# smart-home-weather-station-v1.net
KiCad netlist of a schematic drawn in EasyEDA Pro
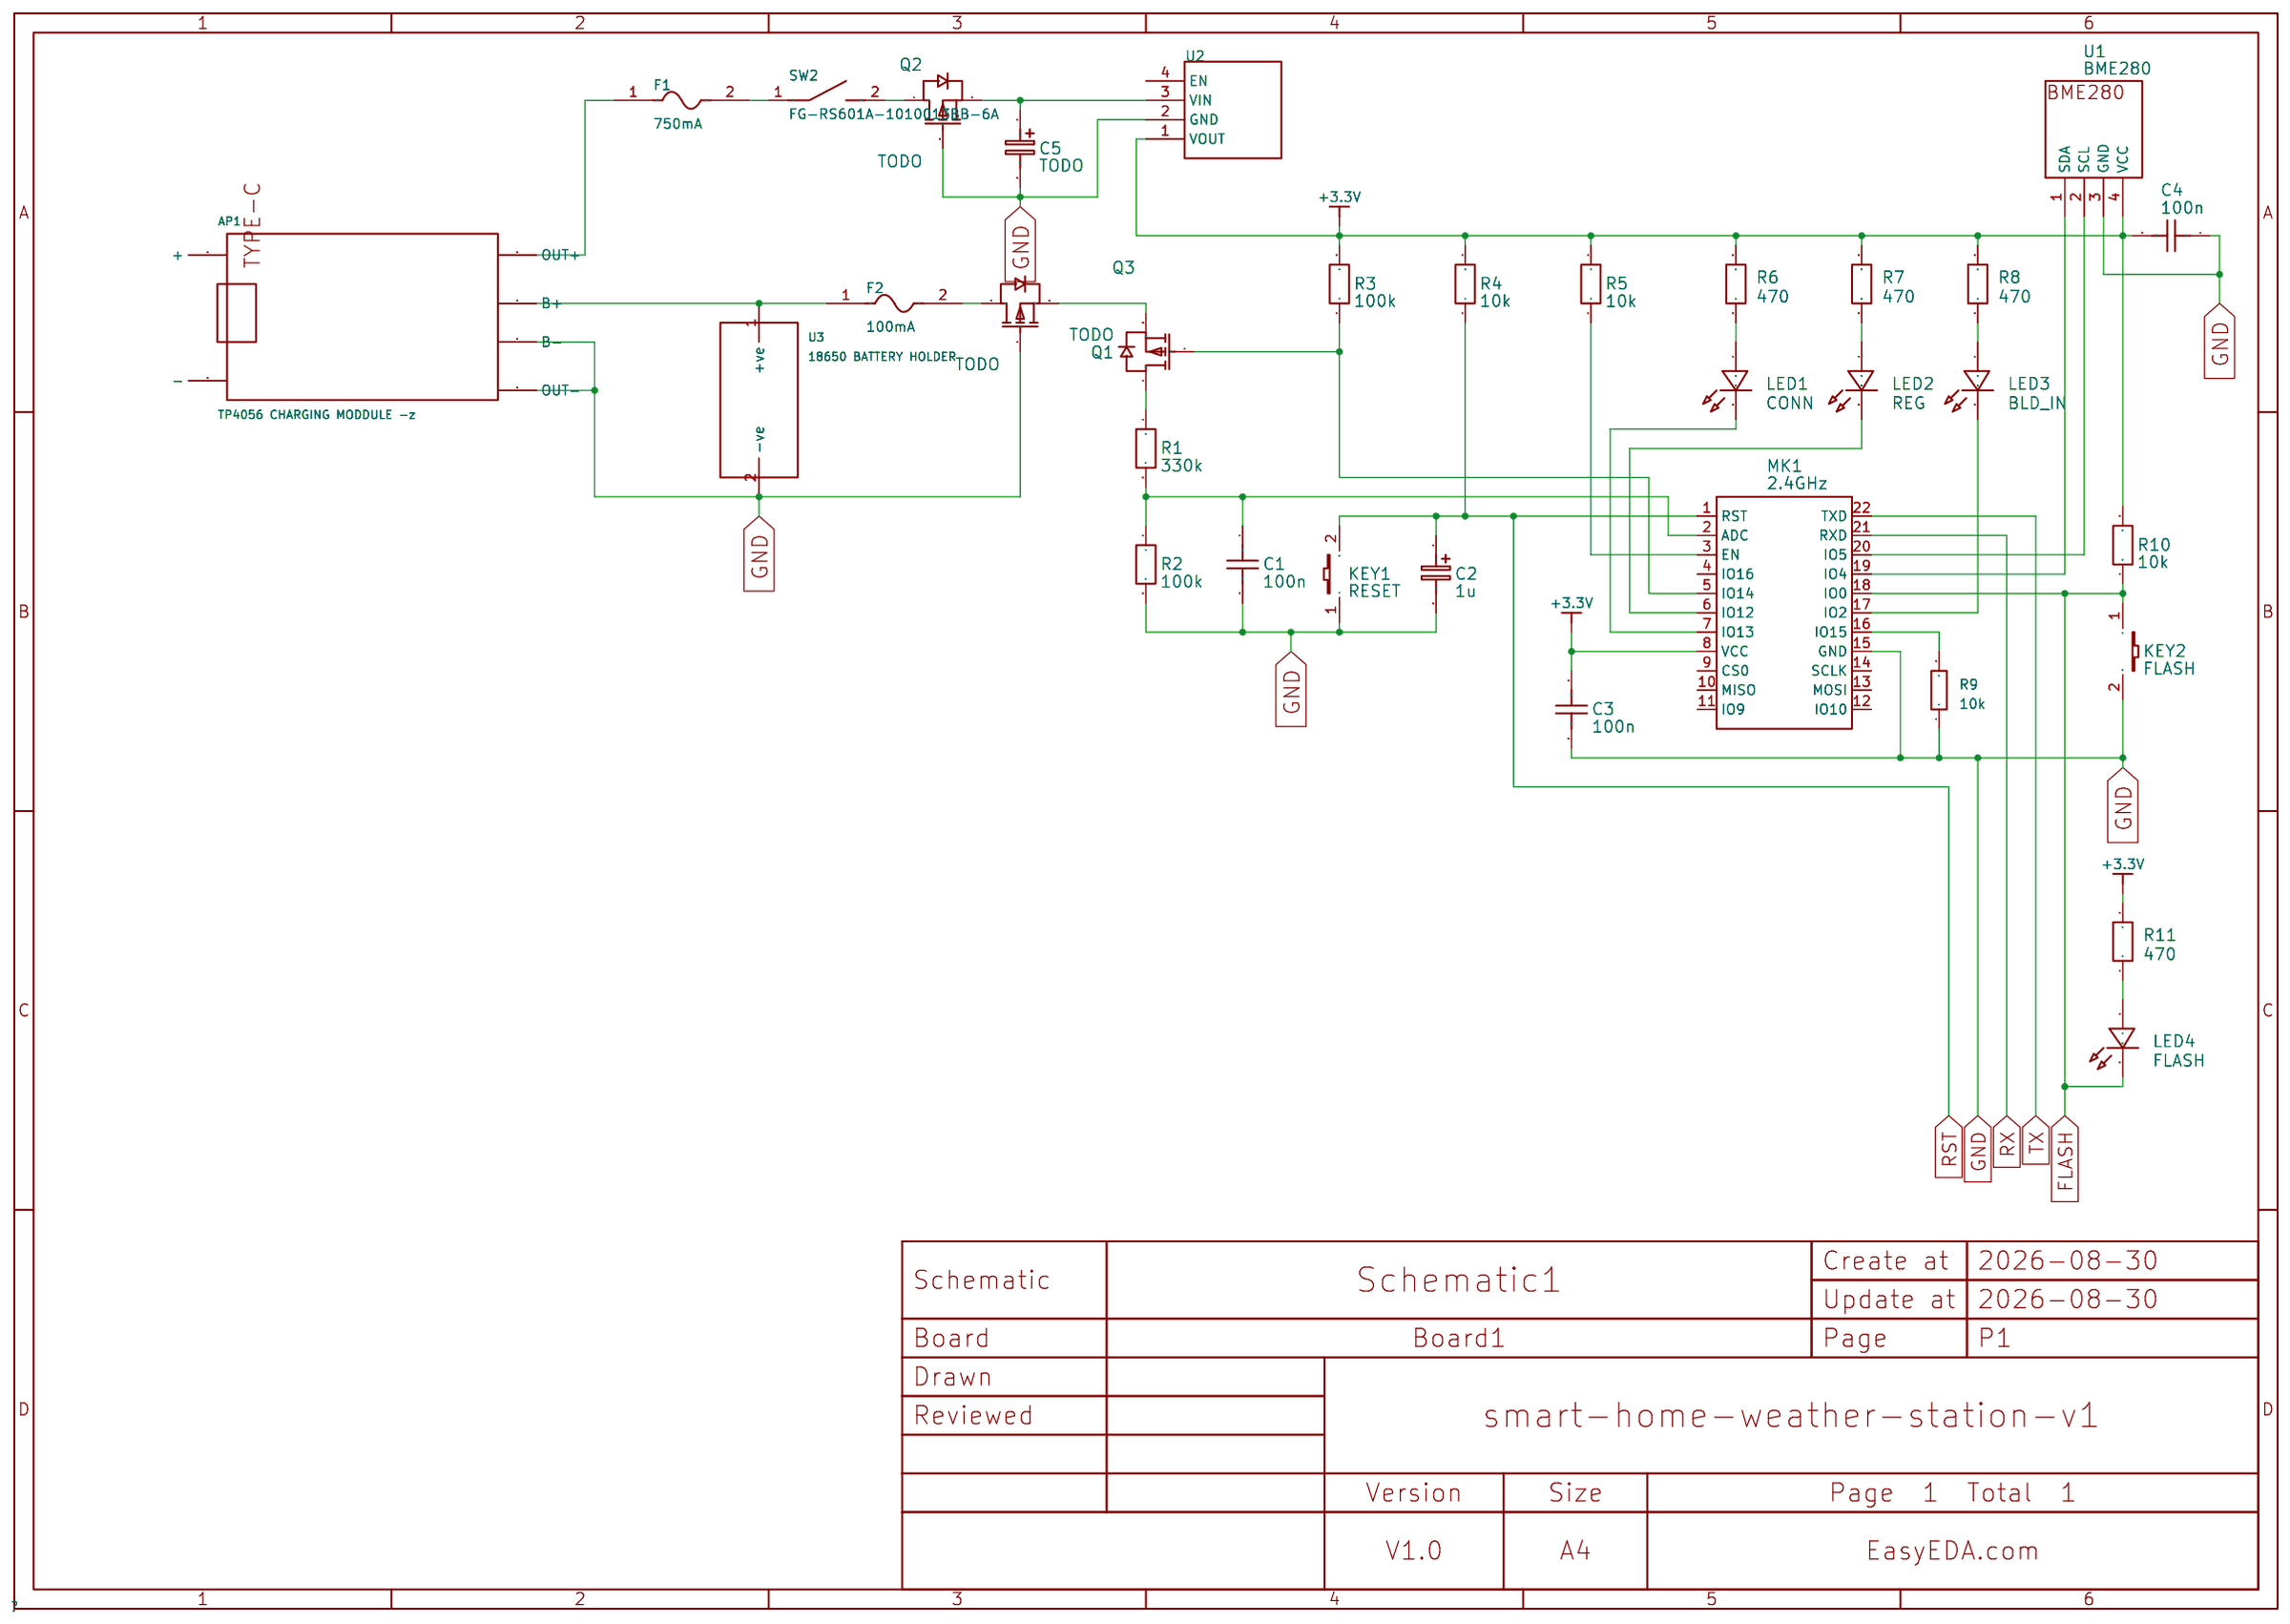
[diagram p0: schematic sheet]

(export (version "E")
  (design (tool "Eeschema 10.0.6"))
  (components
    (comp (ref "AP1")
      (value "TP4056 CHARGING MODDULE -z")
      (footprint "easyedapro:TP4056-CHARGING-MODULE_TP4056")
      (fields (field (name "Manufacturer Part") "TP4056"))
      (libsource (lib "easyedapro") (part "TP4056 CHARGING MODDULE -z"))
    )
    (comp (ref "C1")
      (value "100n")
      (footprint "easyedapro:C0603")
      (libsource (lib "easyedapro") (part "100n"))
    )
    (comp (ref "C2")
      (value "1u")
      (footprint "easyedapro:CASE-A_3216")
      (libsource (lib "easyedapro") (part "1u"))
    )
    (comp (ref "C3")
      (value "100n")
      (footprint "easyedapro:C0603")
      (libsource (lib "easyedapro") (part "100n"))
    )
    (comp (ref "C4")
      (value "100n")
      (footprint "easyedapro:C0603")
      (libsource (lib "easyedapro") (part "100n"))
    )
    (comp (ref "C5")
      (value "TODO")
      (footprint "easyedapro:CASE-A_3216")
      (libsource (lib "easyedapro") (part "1u"))
    )
    (comp (ref "F1")
      (value "750mA")
      (footprint "easyedapro:F1210")
      (fields (field (name "Manufacturer Part") "1210L150/16WR"))
      (libsource (lib "easyedapro") (part "1210L150/16WR_C9900015772"))
    )
    (comp (ref "F2")
      (value "100mA")
      (footprint "easyedapro:F1210")
      (fields (field (name "Manufacturer Part") "1210L150/16WR"))
      (libsource (lib "easyedapro") (part "1210L150/16WR_C9900015772"))
    )
    (comp (ref "KEY1")
      (value "RESET")
      (footprint "easyedapro:KEY-SMD_2P-L6.2-W3.6-LS8.0")
      (fields (field (name "Manufacturer Part") "K2-1107ST-A4SW-06"))
      (libsource (lib "easyedapro") (part "RESET"))
    )
    (comp (ref "KEY2")
      (value "FLASH")
      (footprint "easyedapro:KEY-SMD_2P-L6.2-W3.6-LS8.0")
      (fields (field (name "Manufacturer Part") "K2-1107ST-A4SW-06"))
      (libsource (lib "") (part "FLASH_1"))
    )
    (comp (ref "LED1")
      (value "CONN")
      (footprint "easyedapro:LED0603_RED")
      (fields
        (field (name "Manufacturer Part") "19-217/R6C-AL1M2VY/3T")
        (field (name "Manufacturer") "EVERLIGHT(台湾亿光)")
      )
      (libsource (lib "easyedapro") (part "FLASH"))
    )
    (comp (ref "LED2")
      (value "REG")
      (footprint "easyedapro:LED0603_RED")
      (fields
        (field (name "Manufacturer Part") "19-217/R6C-AL1M2VY/3T")
        (field (name "Manufacturer") "EVERLIGHT(台湾亿光)")
      )
      (libsource (lib "easyedapro") (part "FLASH"))
    )
    (comp (ref "LED3")
      (value "BLD_IN")
      (footprint "easyedapro:LED0603_RED")
      (fields
        (field (name "Manufacturer Part") "19-217/R6C-AL1M2VY/3T")
        (field (name "Manufacturer") "EVERLIGHT(台湾亿光)")
      )
      (libsource (lib "easyedapro") (part "FLASH"))
    )
    (comp (ref "LED4")
      (value "FLASH")
      (footprint "easyedapro:LED0603_RED")
      (fields
        (field (name "Manufacturer Part") "19-217/R6C-AL1M2VY/3T")
        (field (name "Manufacturer") "EVERLIGHT(台湾亿光)")
      )
      (libsource (lib "easyedapro") (part "FLASH"))
    )
    (comp (ref "MK1")
      (value "2.4GHz")
      (footprint "easyedapro:WIFIM-SMD_ESP-12E-BR")
      (fields (field (name "Manufacturer Part") "ESP-12E") (field (name "Manufacturer") "Ai-Thinker(安信可)"))
      (libsource (lib "easyedapro") (part "2.4GHz"))
    )
    (comp (ref "Q1")
      (value "TODO")
      (footprint "easyedapro:TO-263-2_L10.0-W9.1-P5.08-LS15.2-BR")
      (fields (field (name "Manufacturer Part") "IRF5210STRLPBF") (field (name "Manufacturer") "IR"))
      (libsource (lib "easyedapro") (part "TODO"))
    )
    (comp (ref "Q2")
      (value "TODO")
      (footprint "easyedapro:TO-263-2_L10.0-W9.1-P5.08-LS15.2-BR")
      (fields (field (name "Manufacturer Part") "IRF5210STRLPBF") (field (name "Manufacturer") "IR"))
      (libsource (lib "easyedapro") (part "TODO"))
    )
    (comp (ref "Q3")
      (value "TODO")
      (footprint "easyedapro:TO-263-2_L10.0-W9.1-P5.08-LS15.2-BR")
      (fields (field (name "Manufacturer Part") "IRF5210STRLPBF") (field (name "Manufacturer") "IR"))
      (libsource (lib "easyedapro") (part "TODO"))
    )
    (comp (ref "R1")
      (value "330k")
      (footprint "easyedapro:R0603")
      (libsource (lib "easyedapro") (part "330k"))
    )
    (comp (ref "R2")
      (value "100k")
      (footprint "easyedapro:R0603")
      (libsource (lib "easyedapro") (part "100k"))
    )
    (comp (ref "R3")
      (value "100k")
      (footprint "easyedapro:R0603")
      (libsource (lib "easyedapro") (part "100k"))
    )
    (comp (ref "R4") (value "10k") (footprint "easyedapro:R0603") (libsource (lib "easyedapro") (part "10k")))
    (comp (ref "R5") (value "10k") (footprint "easyedapro:R0603") (libsource (lib "easyedapro") (part "10k")))
    (comp (ref "R6") (value "470") (footprint "easyedapro:R0603") (libsource (lib "easyedapro") (part "470")))
    (comp (ref "R7") (value "470") (footprint "easyedapro:R0603") (libsource (lib "easyedapro") (part "470")))
    (comp (ref "R8") (value "470") (footprint "easyedapro:R0603") (libsource (lib "easyedapro") (part "470")))
    (comp (ref "R9") (value "10K") (footprint "easyedapro:R0603") (libsource (lib "easyedapro") (part "Res")))
    (comp (ref "R10")
      (value "10k")
      (footprint "easyedapro:R0603")
      (libsource (lib "easyedapro") (part "10k"))
    )
    (comp (ref "R11")
      (value "470")
      (footprint "easyedapro:R0603")
      (libsource (lib "easyedapro") (part "470"))
    )
    (comp (ref "SW2")
      (value "FG-RS601A-1010013BB-6A")
      (footprint "easyedapro:SW-TH_FG-RS601A-1010013BB-6A")
      (fields (field (name "Manufacturer") "FG(富港)"))
      (libsource (lib "easyedapro") (part "FG-RS601A-1010013BB-6A"))
    )
    (comp (ref "U1") (value "BME280") (libsource (lib "easyedapro") (part "BME280")))
    (comp (ref "U2")
      (value "~")
      (footprint "easyedapro:S8V9F3")
      (libsource (lib "easyedapro") (part "S8V9F3"))
    )
    (comp (ref "U3")
      (value "18650 BATTERY HOLDER")
      (footprint "easyedapro:18650 BATTERY HOLDER CB-18650-PC2")
      (libsource (lib "easyedapro") (part "18650 BATTERY HOLDER"))
    )
  )
  (nets
    (net (code "1") (name "+3.3V") (class "Default")
      (node (ref "C3") (pin "1") (pinfunction "1_1") (pintype "unspecified"))
      (node (ref "C4") (pin "2") (pinfunction "2_2") (pintype "unspecified"))
      (node (ref "MK1") (pin "8") (pinfunction "VCC_8") (pintype "unspecified"))
      (node (ref "R10") (pin "2") (pinfunction "2_2") (pintype "unspecified"))
      (node (ref "R11") (pin "2") (pinfunction "2_2") (pintype "unspecified"))
      (node (ref "R3") (pin "2") (pinfunction "2_2") (pintype "unspecified"))
      (node (ref "R4") (pin "2") (pinfunction "2_2") (pintype "unspecified"))
      (node (ref "R5") (pin "2") (pinfunction "2_2") (pintype "unspecified"))
      (node (ref "R6") (pin "2") (pinfunction "2_2") (pintype "unspecified"))
      (node (ref "R7") (pin "2") (pinfunction "2_2") (pintype "unspecified"))
      (node (ref "R8") (pin "2") (pinfunction "2_2") (pintype "unspecified"))
      (node (ref "U1") (pin "4") (pinfunction "VCC_4") (pintype "unspecified"))
      (node (ref "U2") (pin "1") (pinfunction "VOUT_1") (pintype "input"))
    )
    (net (code "2") (name "FLASH") (class "Default")
      (node (ref "KEY2") (pin "1") (pinfunction "1_1") (pintype "unspecified"))
      (node (ref "LED4") (pin "2") (pinfunction "2_2") (pintype "unspecified"))
      (node (ref "MK1") (pin "18") (pinfunction "IO0_18") (pintype "unspecified"))
      (node (ref "R10") (pin "1") (pinfunction "1_1") (pintype "unspecified"))
    )
    (net (code "3") (name "GND") (class "Default")
      (node (ref "AP1") (pin "2") (pinfunction "B-_2") (pintype "unspecified"))
      (node (ref "AP1") (pin "4") (pinfunction "OUT-_4") (pintype "unspecified"))
      (node (ref "C1") (pin "2") (pinfunction "2_2") (pintype "unspecified"))
      (node (ref "C2") (pin "2") (pinfunction "2_2") (pintype "unspecified"))
      (node (ref "C3") (pin "2") (pinfunction "2_2") (pintype "unspecified"))
      (node (ref "C4") (pin "1") (pinfunction "1_1") (pintype "unspecified"))
      (node (ref "C5") (pin "2") (pinfunction "2_2") (pintype "unspecified"))
      (node (ref "KEY1") (pin "1") (pinfunction "1_1") (pintype "unspecified"))
      (node (ref "KEY2") (pin "2") (pinfunction "2_2") (pintype "unspecified"))
      (node (ref "MK1") (pin "15") (pinfunction "GND_15") (pintype "unspecified"))
      (node (ref "Q2") (pin "1") (pinfunction "G_1") (pintype "unspecified"))
      (node (ref "Q3") (pin "1") (pinfunction "G_1") (pintype "unspecified"))
      (node (ref "R2") (pin "2") (pinfunction "2_2") (pintype "unspecified"))
      (node (ref "R9") (pin "1") (pinfunction "1_1") (pintype "input"))
      (node (ref "U1") (pin "3") (pinfunction "GND_3") (pintype "unspecified"))
      (node (ref "U2") (pin "2") (pinfunction "GND_2") (pintype "input"))
      (node (ref "U3") (pin "2") (pinfunction "-ve_2") (pintype "unspecified"))
    )
    (net (code "4") (name "Net-(AP1-B+)") (class "Default")
      (node (ref "AP1") (pin "1") (pinfunction "B+_1") (pintype "unspecified"))
      (node (ref "F2") (pin "1") (pinfunction "1_1") (pintype "unspecified"))
      (node (ref "U3") (pin "1") (pinfunction "+ve_1") (pintype "unspecified"))
    )
    (net (code "5") (name "Net-(AP1-OUT+)") (class "Default")
      (node (ref "AP1") (pin "3") (pinfunction "OUT+_3") (pintype "unspecified"))
      (node (ref "F1") (pin "1") (pinfunction "1_1") (pintype "unspecified"))
    )
    (net (code "6") (name "Net-(F1-Pad2)") (class "Default")
      (node (ref "F1") (pin "2") (pinfunction "2_2") (pintype "unspecified"))
      (node (ref "SW2") (pin "1") (pinfunction "1_1") (pintype "unspecified"))
    )
    (net (code "7") (name "Net-(LED1-Pad1)") (class "Default")
      (node (ref "LED1") (pin "1") (pinfunction "1_1") (pintype "unspecified"))
      (node (ref "R6") (pin "1") (pinfunction "1_1") (pintype "unspecified"))
    )
    (net (code "8") (name "Net-(LED2-Pad1)") (class "Default")
      (node (ref "LED2") (pin "1") (pinfunction "1_1") (pintype "unspecified"))
      (node (ref "R7") (pin "1") (pinfunction "1_1") (pintype "unspecified"))
    )
    (net (code "9") (name "Net-(LED3-Pad1)") (class "Default")
      (node (ref "LED3") (pin "1") (pinfunction "1_1") (pintype "unspecified"))
      (node (ref "R8") (pin "1") (pinfunction "1_1") (pintype "unspecified"))
    )
    (net (code "10") (name "Net-(LED4-Pad1)") (class "Default")
      (node (ref "LED4") (pin "1") (pinfunction "1_1") (pintype "unspecified"))
      (node (ref "R11") (pin "1") (pinfunction "1_1") (pintype "unspecified"))
    )
    (net (code "11") (name "Net-(MK1-ADC)") (class "Default")
      (node (ref "C1") (pin "1") (pinfunction "1_1") (pintype "unspecified"))
      (node (ref "MK1") (pin "2") (pinfunction "ADC_2") (pintype "unspecified"))
      (node (ref "R1") (pin "2") (pinfunction "2_2") (pintype "unspecified"))
      (node (ref "R2") (pin "1") (pinfunction "1_1") (pintype "unspecified"))
    )
    (net (code "12") (name "Net-(MK1-EN)") (class "Default")
      (node (ref "MK1") (pin "3") (pinfunction "EN_3") (pintype "unspecified"))
      (node (ref "R5") (pin "1") (pinfunction "1_1") (pintype "unspecified"))
    )
    (net (code "13") (name "Net-(MK1-IO2)") (class "Default")
      (node (ref "LED3") (pin "2") (pinfunction "2_2") (pintype "unspecified"))
      (node (ref "MK1") (pin "17") (pinfunction "IO2_17") (pintype "unspecified"))
    )
    (net (code "14") (name "Net-(MK1-IO4)") (class "Default")
      (node (ref "MK1") (pin "19") (pinfunction "IO4_19") (pintype "unspecified"))
      (node (ref "U1") (pin "1") (pinfunction "SDA_1") (pintype "unspecified"))
    )
    (net (code "15") (name "Net-(MK1-IO5)") (class "Default")
      (node (ref "MK1") (pin "20") (pinfunction "IO5_20") (pintype "unspecified"))
      (node (ref "U1") (pin "2") (pinfunction "SCL_2") (pintype "unspecified"))
    )
    (net (code "16") (name "Net-(MK1-IO12)") (class "Default")
      (node (ref "LED2") (pin "2") (pinfunction "2_2") (pintype "unspecified"))
      (node (ref "MK1") (pin "6") (pinfunction "IO12_6") (pintype "unspecified"))
    )
    (net (code "17") (name "Net-(MK1-IO13)") (class "Default")
      (node (ref "LED1") (pin "2") (pinfunction "2_2") (pintype "unspecified"))
      (node (ref "MK1") (pin "7") (pinfunction "IO13_7") (pintype "unspecified"))
    )
    (net (code "18") (name "Net-(MK1-IO14)") (class "Default")
      (node (ref "MK1") (pin "5") (pinfunction "IO14_5") (pintype "unspecified"))
      (node (ref "Q1") (pin "1") (pinfunction "G_1") (pintype "unspecified"))
      (node (ref "R3") (pin "1") (pinfunction "1_1") (pintype "unspecified"))
    )
    (net (code "19") (name "Net-(MK1-IO15)") (class "Default")
      (node (ref "MK1") (pin "16") (pinfunction "IO15_16") (pintype "unspecified"))
      (node (ref "R9") (pin "2") (pinfunction "2_2") (pintype "input"))
    )
    (net (code "20") (name "Net-(Q1-D)") (class "Default")
      (node (ref "Q1") (pin "4") (pinfunction "D_4") (pintype "unspecified"))
      (node (ref "R1") (pin "1") (pinfunction "1_1") (pintype "unspecified"))
    )
    (net (code "21") (name "Net-(Q1-S)") (class "Default")
      (node (ref "Q1") (pin "3") (pinfunction "S_3") (pintype "unspecified"))
      (node (ref "Q3") (pin "3") (pinfunction "S_3") (pintype "unspecified"))
    )
    (net (code "22") (name "Net-(Q2-D)") (class "Default")
      (node (ref "Q2") (pin "4") (pinfunction "D_4") (pintype "unspecified"))
      (node (ref "SW2") (pin "2") (pinfunction "2_2") (pintype "unspecified"))
    )
    (net (code "23") (name "Net-(Q2-S)") (class "Default")
      (node (ref "C5") (pin "1") (pinfunction "1_1") (pintype "unspecified"))
      (node (ref "Q2") (pin "3") (pinfunction "S_3") (pintype "unspecified"))
      (node (ref "U2") (pin "3") (pinfunction "VIN_3") (pintype "input"))
    )
    (net (code "24") (name "Net-(Q3-D)") (class "Default")
      (node (ref "F2") (pin "2") (pinfunction "2_2") (pintype "unspecified"))
      (node (ref "Q3") (pin "4") (pinfunction "D_4") (pintype "unspecified"))
    )
    (net (code "25") (name "RST") (class "Default")
      (node (ref "C2") (pin "1") (pinfunction "1_1") (pintype "unspecified"))
      (node (ref "KEY1") (pin "2") (pinfunction "2_2") (pintype "unspecified"))
      (node (ref "MK1") (pin "1") (pinfunction "RST_1") (pintype "unspecified"))
      (node (ref "R4") (pin "1") (pinfunction "1_1") (pintype "unspecified"))
    )
    (net (code "26") (name "RX") (class "Default")
      (node (ref "MK1") (pin "21") (pinfunction "RXD_21") (pintype "unspecified"))
    )
    (net (code "27") (name "TX") (class "Default")
      (node (ref "MK1") (pin "22") (pinfunction "TXD_22") (pintype "unspecified"))
    )
    (net (code "28") (name "unconnected-(AP1-+-Pad5)") (class "Default")
      (node (ref "AP1") (pin "5") (pinfunction "+_5") (pintype "unspecified"))
    )
    (net (code "29") (name "unconnected-(AP1---Pad6)") (class "Default")
      (node (ref "AP1") (pin "6") (pinfunction "-_6") (pintype "unspecified"))
    )
    (net (code "30") (name "unconnected-(MK1-CS0-Pad9)") (class "Default")
      (node (ref "MK1") (pin "9") (pinfunction "CS0_9") (pintype "unspecified"))
    )
    (net (code "31") (name "unconnected-(MK1-IO9-Pad11)") (class "Default")
      (node (ref "MK1") (pin "11") (pinfunction "IO9_11") (pintype "unspecified"))
    )
    (net (code "32") (name "unconnected-(MK1-IO10-Pad12)") (class "Default")
      (node (ref "MK1") (pin "12") (pinfunction "IO10_12") (pintype "unspecified"))
    )
    (net (code "33") (name "unconnected-(MK1-IO16-Pad4)") (class "Default")
      (node (ref "MK1") (pin "4") (pinfunction "IO16_4") (pintype "unspecified"))
    )
    (net (code "34") (name "unconnected-(MK1-MISO-Pad10)") (class "Default")
      (node (ref "MK1") (pin "10") (pinfunction "MISO_10") (pintype "unspecified"))
    )
    (net (code "35") (name "unconnected-(MK1-MOSI-Pad13)") (class "Default")
      (node (ref "MK1") (pin "13") (pinfunction "MOSI_13") (pintype "unspecified"))
    )
    (net (code "36") (name "unconnected-(MK1-SCLK-Pad14)") (class "Default")
      (node (ref "MK1") (pin "14") (pinfunction "SCLK_14") (pintype "unspecified"))
    )
    (net (code "37") (name "unconnected-(U2-EN-Pad4)") (class "Default")
      (node (ref "U2") (pin "4") (pinfunction "EN_4") (pintype "input"))
    )
  )
)
